# button.net
KiCad netlist of a schematic drawn in EAGLE
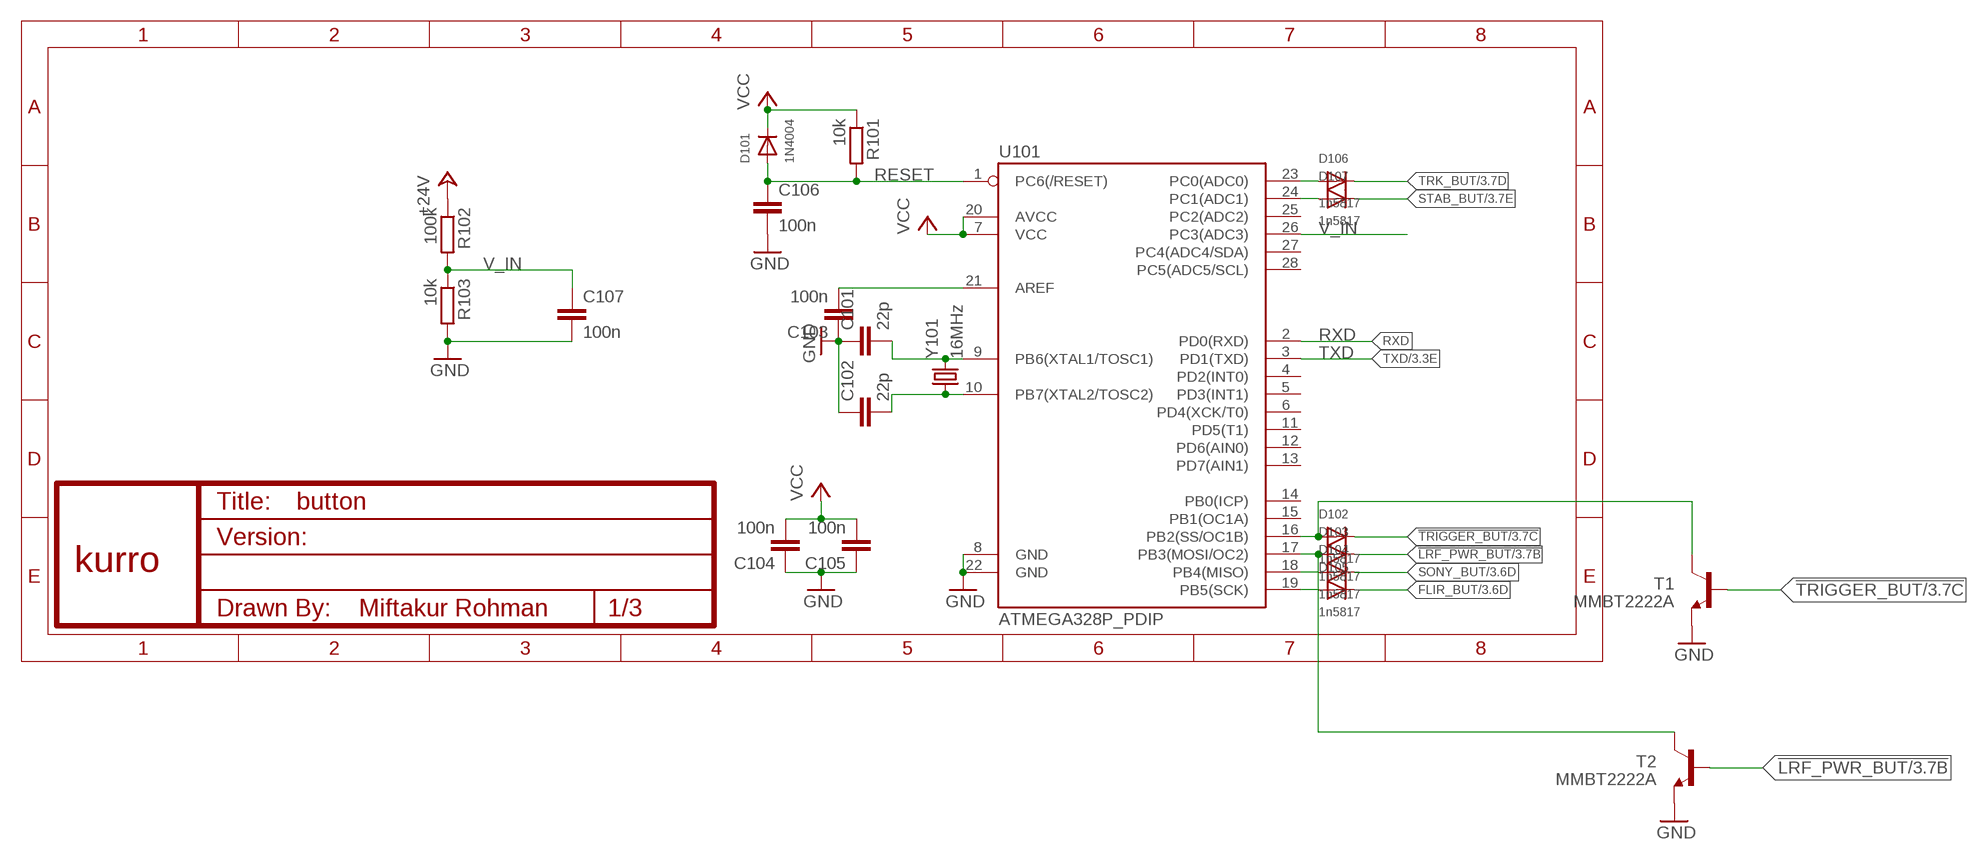
[diagram p0: schematic, sheet 1]
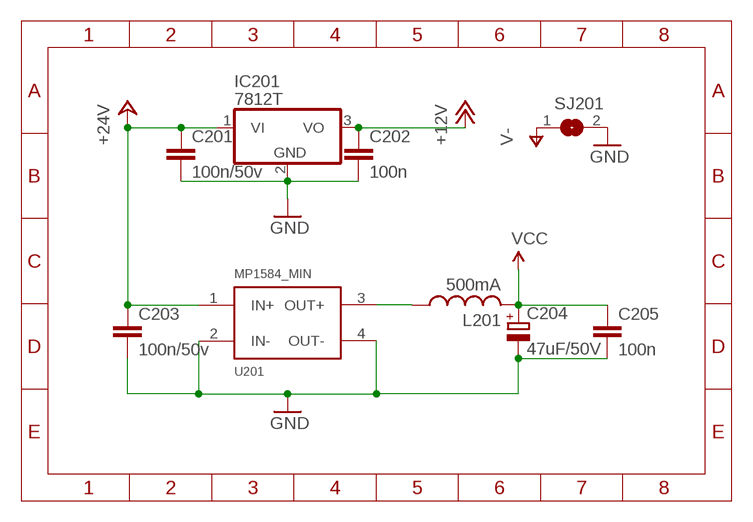
[diagram p1: schematic, sheet 2]
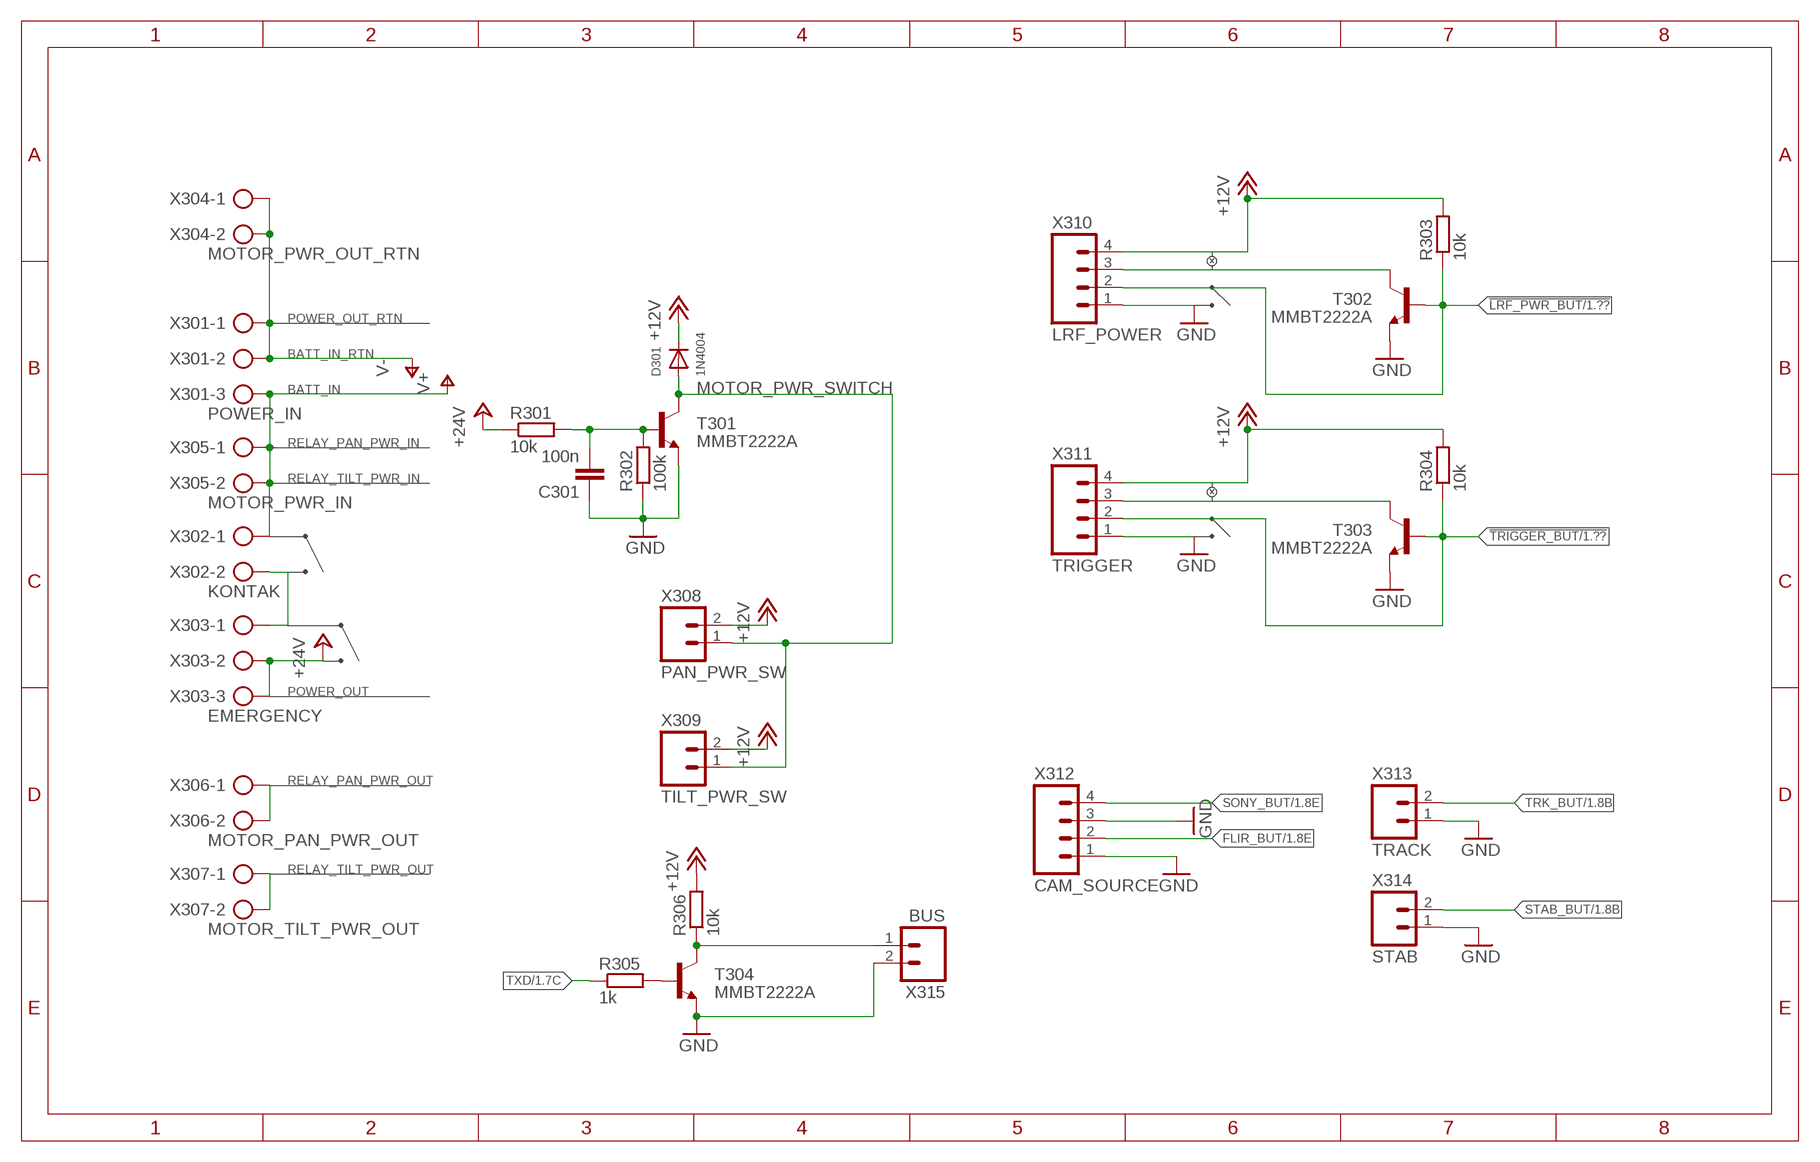
[diagram p2: schematic, sheet 3]

(export (version "E")
  (design (tool "Eeschema 10.0.6"))
  (components
    (comp (ref "C101")
      (value "22p")
      (footprint "eagle-import:C0603")
      (libsource (lib "eagle-import") (part "C-EUC0603"))
    )
    (comp (ref "C102")
      (value "22p")
      (footprint "eagle-import:C0603")
      (libsource (lib "eagle-import") (part "C-EUC0603"))
    )
    (comp (ref "C103")
      (value "100n")
      (footprint "eagle-import:C0603")
      (libsource (lib "eagle-import") (part "C-EUC0603"))
    )
    (comp (ref "C104")
      (value "100n")
      (footprint "eagle-import:C0603")
      (libsource (lib "eagle-import") (part "C-EUC0603"))
    )
    (comp (ref "C105")
      (value "100n")
      (footprint "eagle-import:C0603")
      (libsource (lib "eagle-import") (part "C-EUC0603"))
    )
    (comp (ref "C106")
      (value "100n")
      (footprint "eagle-import:C0603")
      (libsource (lib "eagle-import") (part "C-EUC0603"))
    )
    (comp (ref "C107")
      (value "100n")
      (footprint "eagle-import:C0603")
      (libsource (lib "eagle-import") (part "C-EUC0603"))
    )
    (comp (ref "D101")
      (value "1N4004")
      (footprint "eagle-import:SOD-323F")
      (libsource (lib "eagle-import") (part "DIODESOD-323F"))
    )
    (comp (ref "D102")
      (value "1n5817")
      (footprint "eagle-import:SOD-323F")
      (libsource (lib "eagle-import") (part "DIODESOD-323F"))
    )
    (comp (ref "D103")
      (value "1n5817")
      (footprint "eagle-import:SOD-323F")
      (libsource (lib "eagle-import") (part "DIODESOD-323F"))
    )
    (comp (ref "D104")
      (value "1n5817")
      (footprint "eagle-import:SOD-323F")
      (libsource (lib "eagle-import") (part "DIODESOD-323F"))
    )
    (comp (ref "D105")
      (value "1n5817")
      (footprint "eagle-import:SOD-323F")
      (libsource (lib "eagle-import") (part "DIODESOD-323F"))
    )
    (comp (ref "D106")
      (value "1n5817")
      (footprint "eagle-import:SOD-323F")
      (libsource (lib "eagle-import") (part "DIODESOD-323F"))
    )
    (comp (ref "D107")
      (value "1n5817")
      (footprint "eagle-import:SOD-323F")
      (libsource (lib "eagle-import") (part "DIODESOD-323F"))
    )
    (comp (ref "R101")
      (value "10k")
      (footprint "eagle-import:R0603")
      (libsource (lib "eagle-import") (part "R-EU_R0603"))
    )
    (comp (ref "R102")
      (value "100k")
      (footprint "eagle-import:R0603")
      (libsource (lib "eagle-import") (part "R-EU_R0603"))
    )
    (comp (ref "R103")
      (value "10k")
      (footprint "eagle-import:R0603")
      (libsource (lib "eagle-import") (part "R-EU_R0603"))
    )
    (comp (ref "T1")
      (value "MMBT2222A")
      (footprint "eagle-import:SOT23")
      (libsource (lib "eagle-import") (part "TRANSISTOR_NPNSOT23"))
    )
    (comp (ref "T2")
      (value "MMBT2222A")
      (footprint "eagle-import:SOT23")
      (libsource (lib "eagle-import") (part "TRANSISTOR_NPNSOT23"))
    )
    (comp (ref "U$1")
      (value "KURRO_FOOTPRINT")
      (footprint "eagle-import:KURRO-LOGO")
      (libsource (lib "eagle-import") (part "KURRO_FOOTPRINT"))
    )
    (comp (ref "U101")
      (value "ATMEGA328P_PDIP")
      (footprint "eagle-import:DIL28-3")
      (libsource (lib "eagle-import") (part "ATMEGA328P_PDIP"))
    )
    (comp (ref "Y101")
      (value "16MHz")
      (footprint "eagle-import:CRYSTAL-TXC-7A2")
      (libsource (lib "eagle-import") (part "CRYSTAL-TXC-7A2"))
    )
    (comp (ref "C301")
      (value "100n")
      (footprint "eagle-import:C0603")
      (libsource (lib "eagle-import") (part "C-EUC0603"))
    )
    (comp (ref "D301")
      (value "1N4004")
      (footprint "eagle-import:SOD-323F")
      (libsource (lib "eagle-import") (part "DIODESOD-323F"))
    )
    (comp (ref "R301")
      (value "10k")
      (footprint "eagle-import:R0603")
      (libsource (lib "eagle-import") (part "R-EU_R0603"))
    )
    (comp (ref "R302")
      (value "100k")
      (footprint "eagle-import:R0603")
      (libsource (lib "eagle-import") (part "R-EU_R0603"))
    )
    (comp (ref "R303")
      (value "10k")
      (footprint "eagle-import:R0603")
      (libsource (lib "eagle-import") (part "R-EU_R0603"))
    )
    (comp (ref "R304")
      (value "10k")
      (footprint "eagle-import:R0603")
      (libsource (lib "eagle-import") (part "R-EU_R0603"))
    )
    (comp (ref "R305")
      (value "1k")
      (footprint "eagle-import:R0603")
      (libsource (lib "eagle-import") (part "R-EU_R0603"))
    )
    (comp (ref "R306")
      (value "10k")
      (footprint "eagle-import:R0603")
      (libsource (lib "eagle-import") (part "R-EU_R0603"))
    )
    (comp (ref "T301")
      (value "MMBT2222A")
      (footprint "eagle-import:SOT23")
      (libsource (lib "eagle-import") (part "TRANSISTOR_NPNSOT23"))
    )
    (comp (ref "T302")
      (value "MMBT2222A")
      (footprint "eagle-import:SOT23")
      (libsource (lib "eagle-import") (part "TRANSISTOR_NPNSOT23"))
    )
    (comp (ref "T303")
      (value "MMBT2222A")
      (footprint "eagle-import:SOT23")
      (libsource (lib "eagle-import") (part "TRANSISTOR_NPNSOT23"))
    )
    (comp (ref "T304")
      (value "MMBT2222A")
      (footprint "eagle-import:SOT23")
      (libsource (lib "eagle-import") (part "TRANSISTOR_NPNSOT23"))
    )
    (comp (ref "X301")
      (value "POWER_IN")
      (footprint "eagle-import:AK300_3")
      (libsource (lib "eagle-import") (part "AK300/3"))
    )
    (comp (ref "X302")
      (value "KONTAK")
      (footprint "eagle-import:AK300_2")
      (libsource (lib "eagle-import") (part "AK300/2"))
    )
    (comp (ref "X303")
      (value "EMERGENCY")
      (footprint "eagle-import:AK300_3")
      (libsource (lib "eagle-import") (part "AK300/3"))
    )
    (comp (ref "X304")
      (value "MOTOR_PWR_OUT_RTN")
      (footprint "eagle-import:AK300_2")
      (libsource (lib "eagle-import") (part "AK300/2"))
    )
    (comp (ref "X305")
      (value "MOTOR_PWR_IN")
      (footprint "eagle-import:AK300_2")
      (libsource (lib "eagle-import") (part "AK300/2"))
    )
    (comp (ref "X306")
      (value "MOTOR_PAN_PWR_OUT")
      (footprint "eagle-import:AK300_2")
      (libsource (lib "eagle-import") (part "AK300/2"))
    )
    (comp (ref "X307")
      (value "MOTOR_TILT_PWR_OUT")
      (footprint "eagle-import:AK300_2")
      (libsource (lib "eagle-import") (part "AK300/2"))
    )
    (comp (ref "X308")
      (value "PAN_PWR_SW")
      (footprint "eagle-import:JST-2-PTH-VERT")
      (libsource (lib "eagle-import") (part "M02JST-PTH-VERT"))
    )
    (comp (ref "X309")
      (value "TILT_PWR_SW")
      (footprint "eagle-import:JST-2-PTH-VERT")
      (libsource (lib "eagle-import") (part "M02JST-PTH-VERT"))
    )
    (comp (ref "X310")
      (value "LRF_POWER")
      (footprint "eagle-import:JST-4-PTH-VERT")
      (libsource (lib "eagle-import") (part "M04JST-PTH-VERT"))
    )
    (comp (ref "X311")
      (value "TRIGGER")
      (footprint "eagle-import:JST-4-PTH-VERT")
      (libsource (lib "eagle-import") (part "M04JST-PTH-VERT"))
    )
    (comp (ref "X312")
      (value "CAM_SOURCE")
      (footprint "eagle-import:JST-4-PTH-VERT")
      (libsource (lib "eagle-import") (part "M04JST-PTH-VERT"))
    )
    (comp (ref "X313")
      (value "TRACK")
      (footprint "eagle-import:JST-2-PTH-VERT")
      (libsource (lib "eagle-import") (part "M02JST-PTH-VERT"))
    )
    (comp (ref "X314")
      (value "STAB")
      (footprint "eagle-import:JST-2-PTH-VERT")
      (libsource (lib "eagle-import") (part "M02JST-PTH-VERT"))
    )
    (comp (ref "X315")
      (value "BUS")
      (footprint "eagle-import:JST-2-PTH-VERT")
      (libsource (lib "eagle-import") (part "M02JST-PTH-VERT"))
    )
    (comp (ref "C201")
      (value "100n/50v")
      (footprint "eagle-import:C0603")
      (libsource (lib "eagle-import") (part "C-EUC0603"))
    )
    (comp (ref "C202")
      (value "100n")
      (footprint "eagle-import:C0603")
      (libsource (lib "eagle-import") (part "C-EUC0603"))
    )
    (comp (ref "C203")
      (value "100n/50v")
      (footprint "eagle-import:C0603")
      (libsource (lib "eagle-import") (part "C-EUC0603"))
    )
    (comp (ref "C204")
      (value "47uF/50V")
      (footprint "eagle-import:E2,5-7")
      (libsource (lib "eagle-import") (part "CPOL-EUE2.5-7"))
    )
    (comp (ref "C205")
      (value "100n")
      (footprint "eagle-import:C0603")
      (libsource (lib "eagle-import") (part "C-EUC0603"))
    )
    (comp (ref "IC201")
      (value "7812T")
      (footprint "eagle-import:TO220H")
      (libsource (lib "eagle-import") (part "78T12"))
    )
    (comp (ref "L201")
      (value "500mA")
      (footprint "eagle-import:L1812")
      (libsource (lib "eagle-import") (part "L-USL1812"))
    )
    (comp (ref "SJ201")
      (value "SJ")
      (footprint "eagle-import:SJ")
      (libsource (lib "eagle-import") (part "SJ"))
    )
    (comp (ref "U201")
      (value "MP1584_MIN")
      (footprint "eagle-import:MP1584_MIN")
      (libsource (lib "eagle-import") (part "MP1584_MIN"))
    )
  )
  (nets
    (net (code "1") (name "+12V") (class "Default")
      (node (ref "C202") (pin "1") (pinfunction "1_1") (pintype "passive"))
      (node (ref "D301") (pin "C") (pinfunction "C_C") (pintype "passive"))
      (node (ref "IC201") (pin "3") (pinfunction "VO_3") (pintype "passive"))
      (node (ref "R303") (pin "2") (pinfunction "2_2") (pintype "passive"))
      (node (ref "R304") (pin "2") (pinfunction "2_2") (pintype "passive"))
      (node (ref "R306") (pin "2") (pinfunction "2_2") (pintype "passive"))
      (node (ref "X308") (pin "2") (pinfunction "2_2") (pintype "passive"))
      (node (ref "X309") (pin "2") (pinfunction "2_2") (pintype "passive"))
      (node (ref "X310") (pin "4") (pinfunction "4_4") (pintype "passive"))
      (node (ref "X311") (pin "4") (pinfunction "4_4") (pintype "passive"))
    )
    (net (code "2") (name "+24V") (class "Default")
      (node (ref "C201") (pin "1") (pinfunction "1_1") (pintype "passive"))
      (node (ref "C203") (pin "1") (pinfunction "1_1") (pintype "passive"))
      (node (ref "IC201") (pin "1") (pinfunction "VI_1") (pintype "input"))
      (node (ref "R102") (pin "1") (pinfunction "1_1") (pintype "passive"))
      (node (ref "R301") (pin "1") (pinfunction "1_1") (pintype "passive"))
      (node (ref "U201") (pin "1") (pinfunction "IN+_1") (pintype "bidirectional"))
      (node (ref "X303") (pin "2") (pinfunction "KL_2") (pintype "passive"))
      (node (ref "X303") (pin "3") (pinfunction "KL_3") (pintype "passive"))
    )
    (net (code "3") (name "FLIR_BUT") (class "Default")
      (node (ref "D105") (pin "C") (pinfunction "C_C") (pintype "passive"))
      (node (ref "X312") (pin "2") (pinfunction "2_2") (pintype "passive"))
    )
    (net (code "4") (name "GND") (class "Default")
      (node (ref "C101") (pin "1") (pinfunction "1_1") (pintype "passive"))
      (node (ref "C102") (pin "1") (pinfunction "1_1") (pintype "passive"))
      (node (ref "C103") (pin "1") (pinfunction "1_1") (pintype "passive"))
      (node (ref "C104") (pin "1") (pinfunction "1_1") (pintype "passive"))
      (node (ref "C105") (pin "1") (pinfunction "1_1") (pintype "passive"))
      (node (ref "C106") (pin "2") (pinfunction "2_2") (pintype "passive"))
      (node (ref "C107") (pin "2") (pinfunction "2_2") (pintype "passive"))
      (node (ref "C201") (pin "2") (pinfunction "2_2") (pintype "passive"))
      (node (ref "C202") (pin "2") (pinfunction "2_2") (pintype "passive"))
      (node (ref "C203") (pin "2") (pinfunction "2_2") (pintype "passive"))
      (node (ref "C204") (pin "-") (pinfunction "-_-") (pintype "passive"))
      (node (ref "C205") (pin "2") (pinfunction "2_2") (pintype "passive"))
      (node (ref "C301") (pin "1") (pinfunction "1_1") (pintype "passive"))
      (node (ref "IC201") (pin "2") (pinfunction "GND_2") (pintype "passive"))
      (node (ref "R103") (pin "2") (pinfunction "2_2") (pintype "passive"))
      (node (ref "R302") (pin "1") (pinfunction "1_1") (pintype "passive"))
      (node (ref "SJ201") (pin "2") (pinfunction "2_2") (pintype "passive"))
      (node (ref "T1") (pin "2") (pinfunction "E_2") (pintype "passive"))
      (node (ref "T2") (pin "2") (pinfunction "E_2") (pintype "passive"))
      (node (ref "T301") (pin "2") (pinfunction "E_2") (pintype "passive"))
      (node (ref "T302") (pin "2") (pinfunction "E_2") (pintype "passive"))
      (node (ref "T303") (pin "2") (pinfunction "E_2") (pintype "passive"))
      (node (ref "T304") (pin "2") (pinfunction "E_2") (pintype "passive"))
      (node (ref "U101") (pin "22") (pinfunction "GND_22") (pintype "bidirectional"))
      (node (ref "U101") (pin "8") (pinfunction "GND_8") (pintype "bidirectional"))
      (node (ref "U201") (pin "2") (pinfunction "IN-_2") (pintype "bidirectional"))
      (node (ref "U201") (pin "4") (pinfunction "OUT-_4") (pintype "bidirectional"))
      (node (ref "X310") (pin "1") (pinfunction "1_1") (pintype "passive"))
      (node (ref "X311") (pin "1") (pinfunction "1_1") (pintype "passive"))
      (node (ref "X312") (pin "1") (pinfunction "1_1") (pintype "passive"))
      (node (ref "X312") (pin "3") (pinfunction "3_3") (pintype "passive"))
      (node (ref "X313") (pin "1") (pinfunction "1_1") (pintype "passive"))
      (node (ref "X314") (pin "1") (pinfunction "1_1") (pintype "passive"))
      (node (ref "X315") (pin "2") (pinfunction "2_2") (pintype "passive"))
    )
    (net (code "5") (name "MOTOR_PWR_SWITCH") (class "Default")
      (node (ref "D301") (pin "A") (pinfunction "A_A") (pintype "passive"))
      (node (ref "T301") (pin "3") (pinfunction "C_3") (pintype "passive"))
      (node (ref "X308") (pin "1") (pinfunction "1_1") (pintype "passive"))
      (node (ref "X309") (pin "1") (pinfunction "1_1") (pintype "passive"))
    )
    (net (code "6") (name "Net-(T1-C)") (class "Default")
      (node (ref "D102") (pin "A") (pinfunction "A_A") (pintype "passive"))
      (node (ref "T1") (pin "3") (pinfunction "C_3") (pintype "passive"))
      (node (ref "U101") (pin "16") (pinfunction "PB2(SS/OC1B)_16") (pintype "bidirectional"))
    )
    (net (code "7") (name "Net-(T2-C)") (class "Default")
      (node (ref "D103") (pin "A") (pinfunction "A_A") (pintype "passive"))
      (node (ref "T2") (pin "3") (pinfunction "C_3") (pintype "passive"))
      (node (ref "U101") (pin "17") (pinfunction "PB3(MOSI/OC2)_17") (pintype "bidirectional"))
    )
    (net (code "8") (name "Net-(T301-B)") (class "Default")
      (node (ref "C301") (pin "2") (pinfunction "2_2") (pintype "passive"))
      (node (ref "R301") (pin "2") (pinfunction "2_2") (pintype "passive"))
      (node (ref "R302") (pin "2") (pinfunction "2_2") (pintype "passive"))
      (node (ref "T301") (pin "1") (pinfunction "B_1") (pintype "passive"))
    )
    (net (code "9") (name "Net-(T302-C)") (class "Default")
      (node (ref "T302") (pin "3") (pinfunction "C_3") (pintype "passive"))
      (node (ref "X310") (pin "3") (pinfunction "3_3") (pintype "passive"))
    )
    (net (code "10") (name "Net-(T303-C)") (class "Default")
      (node (ref "T303") (pin "3") (pinfunction "C_3") (pintype "passive"))
      (node (ref "X311") (pin "3") (pinfunction "3_3") (pintype "passive"))
    )
    (net (code "11") (name "Net-(T304-B)") (class "Default")
      (node (ref "R305") (pin "2") (pinfunction "2_2") (pintype "passive"))
      (node (ref "T304") (pin "1") (pinfunction "B_1") (pintype "passive"))
    )
    (net (code "12") (name "Net-(T304-C)") (class "Default")
      (node (ref "R306") (pin "1") (pinfunction "1_1") (pintype "passive"))
      (node (ref "T304") (pin "3") (pinfunction "C_3") (pintype "passive"))
      (node (ref "X315") (pin "1") (pinfunction "1_1") (pintype "passive"))
    )
    (net (code "13") (name "Net-(U101-AREF)") (class "Default")
      (node (ref "C103") (pin "2") (pinfunction "2_2") (pintype "passive"))
      (node (ref "U101") (pin "21") (pinfunction "AREF_21") (pintype "bidirectional"))
    )
    (net (code "14") (name "Net-(U101-PB4(MISO))") (class "Default")
      (node (ref "D104") (pin "A") (pinfunction "A_A") (pintype "passive"))
      (node (ref "U101") (pin "18") (pinfunction "PB4(MISO)_18") (pintype "bidirectional"))
    )
    (net (code "15") (name "Net-(U101-PB5(SCK))") (class "Default")
      (node (ref "D105") (pin "A") (pinfunction "A_A") (pintype "passive"))
      (node (ref "U101") (pin "19") (pinfunction "PB5(SCK)_19") (pintype "bidirectional"))
    )
    (net (code "16") (name "Net-(U101-PB6(XTAL1{slash}TOSC1))") (class "Default")
      (node (ref "C101") (pin "2") (pinfunction "2_2") (pintype "passive"))
      (node (ref "U101") (pin "9") (pinfunction "PB6(XTAL1/TOSC1)_9") (pintype "bidirectional"))
      (node (ref "Y101") (pin "P$2") (pinfunction "2_P$2") (pintype "passive"))
    )
    (net (code "17") (name "Net-(U101-PB7(XTAL2{slash}TOSC2))") (class "Default")
      (node (ref "C102") (pin "2") (pinfunction "2_2") (pintype "passive"))
      (node (ref "U101") (pin "10") (pinfunction "PB7(XTAL2/TOSC2)_10") (pintype "bidirectional"))
      (node (ref "Y101") (pin "P$1") (pinfunction "1_P$1") (pintype "passive"))
    )
    (net (code "18") (name "Net-(U101-PC0(ADC0))") (class "Default")
      (node (ref "D106") (pin "A") (pinfunction "A_A") (pintype "passive"))
      (node (ref "U101") (pin "23") (pinfunction "PC0(ADC0)_23") (pintype "bidirectional"))
    )
    (net (code "19") (name "Net-(U101-PC1(ADC1))") (class "Default")
      (node (ref "D107") (pin "A") (pinfunction "A_A") (pintype "passive"))
      (node (ref "U101") (pin "24") (pinfunction "PC1(ADC1)_24") (pintype "bidirectional"))
    )
    (net (code "20") (name "Net-(U201-OUT+)") (class "Default")
      (node (ref "L201") (pin "1") (pinfunction "1_1") (pintype "passive"))
      (node (ref "U201") (pin "3") (pinfunction "OUT+_3") (pintype "bidirectional"))
    )
    (net (code "21") (name "Net-(X302B-KL)") (class "Default")
      (node (ref "X302") (pin "2") (pinfunction "KL_2") (pintype "passive"))
      (node (ref "X303") (pin "1") (pinfunction "KL_1") (pintype "passive"))
    )
    (net (code "22") (name "Net-(X306A-KL)") (class "Default")
      (node (ref "X306") (pin "1") (pinfunction "KL_1") (pintype "passive"))
      (node (ref "X306") (pin "2") (pinfunction "KL_2") (pintype "passive"))
    )
    (net (code "23") (name "Net-(X307A-KL)") (class "Default")
      (node (ref "X307") (pin "1") (pinfunction "KL_1") (pintype "passive"))
      (node (ref "X307") (pin "2") (pinfunction "KL_2") (pintype "passive"))
    )
    (net (code "24") (name "RESET") (class "Default")
      (node (ref "C106") (pin "1") (pinfunction "1_1") (pintype "passive"))
      (node (ref "D101") (pin "A") (pinfunction "A_A") (pintype "passive"))
      (node (ref "R101") (pin "2") (pinfunction "2_2") (pintype "passive"))
      (node (ref "U101") (pin "1") (pinfunction "PC6(/RESET)_1") (pintype "bidirectional"))
    )
    (net (code "25") (name "RXD") (class "Default")
      (node (ref "U101") (pin "2") (pinfunction "PD0(RXD)_2") (pintype "bidirectional"))
    )
    (net (code "26") (name "SONY_BUT") (class "Default")
      (node (ref "D104") (pin "C") (pinfunction "C_C") (pintype "passive"))
      (node (ref "X312") (pin "4") (pinfunction "4_4") (pintype "passive"))
    )
    (net (code "27") (name "STAB_BUT") (class "Default")
      (node (ref "D107") (pin "C") (pinfunction "C_C") (pintype "passive"))
      (node (ref "X314") (pin "2") (pinfunction "2_2") (pintype "passive"))
    )
    (net (code "28") (name "TRK_BUT") (class "Default")
      (node (ref "D106") (pin "C") (pinfunction "C_C") (pintype "passive"))
      (node (ref "X313") (pin "2") (pinfunction "2_2") (pintype "passive"))
    )
    (net (code "29") (name "TXD") (class "Default")
      (node (ref "R305") (pin "1") (pinfunction "1_1") (pintype "passive"))
      (node (ref "U101") (pin "3") (pinfunction "PD1(TXD)_3") (pintype "bidirectional"))
    )
    (net (code "30") (name "V+") (class "Default")
      (node (ref "X301") (pin "3") (pinfunction "KL_3") (pintype "passive"))
      (node (ref "X302") (pin "1") (pinfunction "KL_1") (pintype "passive"))
      (node (ref "X305") (pin "1") (pinfunction "KL_1") (pintype "passive"))
      (node (ref "X305") (pin "2") (pinfunction "KL_2") (pintype "passive"))
    )
    (net (code "31") (name "V-") (class "Default")
      (node (ref "SJ201") (pin "1") (pinfunction "1_1") (pintype "passive"))
      (node (ref "X301") (pin "1") (pinfunction "KL_1") (pintype "passive"))
      (node (ref "X301") (pin "2") (pinfunction "KL_2") (pintype "passive"))
      (node (ref "X304") (pin "1") (pinfunction "KL_1") (pintype "passive"))
      (node (ref "X304") (pin "2") (pinfunction "KL_2") (pintype "passive"))
    )
    (net (code "32") (name "VCC") (class "Default")
      (node (ref "C104") (pin "2") (pinfunction "2_2") (pintype "passive"))
      (node (ref "C105") (pin "2") (pinfunction "2_2") (pintype "passive"))
      (node (ref "C204") (pin "+") (pinfunction "+_+") (pintype "passive"))
      (node (ref "C205") (pin "1") (pinfunction "1_1") (pintype "passive"))
      (node (ref "D101") (pin "C") (pinfunction "C_C") (pintype "passive"))
      (node (ref "L201") (pin "2") (pinfunction "2_2") (pintype "passive"))
      (node (ref "R101") (pin "1") (pinfunction "1_1") (pintype "passive"))
      (node (ref "U101") (pin "20") (pinfunction "AVCC_20") (pintype "bidirectional"))
      (node (ref "U101") (pin "7") (pinfunction "VCC_7") (pintype "bidirectional"))
    )
    (net (code "33") (name "V_IN") (class "Default")
      (node (ref "C107") (pin "1") (pinfunction "1_1") (pintype "passive"))
      (node (ref "R102") (pin "2") (pinfunction "2_2") (pintype "passive"))
      (node (ref "R103") (pin "1") (pinfunction "1_1") (pintype "passive"))
      (node (ref "U101") (pin "26") (pinfunction "PC3(ADC3)_26") (pintype "bidirectional"))
    )
    (net (code "34") (name "unconnected-(U101-PB0(ICP)-Pad14)") (class "Default")
      (node (ref "U101") (pin "14") (pinfunction "PB0(ICP)_14") (pintype "bidirectional"))
    )
    (net (code "35") (name "unconnected-(U101-PB1(OC1A)-Pad15)") (class "Default")
      (node (ref "U101") (pin "15") (pinfunction "PB1(OC1A)_15") (pintype "bidirectional"))
    )
    (net (code "36") (name "unconnected-(U101-PC2(ADC2)-Pad25)") (class "Default")
      (node (ref "U101") (pin "25") (pinfunction "PC2(ADC2)_25") (pintype "bidirectional"))
    )
    (net (code "37") (name "unconnected-(U101-PC4(ADC4{slash}SDA)-Pad27)") (class "Default")
      (node (ref "U101") (pin "27") (pinfunction "PC4(ADC4/SDA)_27") (pintype "bidirectional"))
    )
    (net (code "38") (name "unconnected-(U101-PC5(ADC5{slash}SCL)-Pad28)") (class "Default")
      (node (ref "U101") (pin "28") (pinfunction "PC5(ADC5/SCL)_28") (pintype "bidirectional"))
    )
    (net (code "39") (name "unconnected-(U101-PD2(INT0)-Pad4)") (class "Default")
      (node (ref "U101") (pin "4") (pinfunction "PD2(INT0)_4") (pintype "bidirectional"))
    )
    (net (code "40") (name "unconnected-(U101-PD3(INT1)-Pad5)") (class "Default")
      (node (ref "U101") (pin "5") (pinfunction "PD3(INT1)_5") (pintype "bidirectional"))
    )
    (net (code "41") (name "unconnected-(U101-PD4(XCK{slash}T0)-Pad6)") (class "Default")
      (node (ref "U101") (pin "6") (pinfunction "PD4(XCK/T0)_6") (pintype "bidirectional"))
    )
    (net (code "42") (name "unconnected-(U101-PD5(T1)-Pad11)") (class "Default")
      (node (ref "U101") (pin "11") (pinfunction "PD5(T1)_11") (pintype "bidirectional"))
    )
    (net (code "43") (name "unconnected-(U101-PD6(AIN0)-Pad12)") (class "Default")
      (node (ref "U101") (pin "12") (pinfunction "PD6(AIN0)_12") (pintype "bidirectional"))
    )
    (net (code "44") (name "unconnected-(U101-PD7(AIN1)-Pad13)") (class "Default")
      (node (ref "U101") (pin "13") (pinfunction "PD7(AIN1)_13") (pintype "bidirectional"))
    )
    (net (code "45") (name "~{LRF_PWR_BUT}") (class "Default")
      (node (ref "D103") (pin "C") (pinfunction "C_C") (pintype "passive"))
      (node (ref "R303") (pin "1") (pinfunction "1_1") (pintype "passive"))
      (node (ref "T2") (pin "1") (pinfunction "B_1") (pintype "passive"))
      (node (ref "T302") (pin "1") (pinfunction "B_1") (pintype "passive"))
      (node (ref "X310") (pin "2") (pinfunction "2_2") (pintype "passive"))
    )
    (net (code "46") (name "~{TRIGGER_BUT}") (class "Default")
      (node (ref "D102") (pin "C") (pinfunction "C_C") (pintype "passive"))
      (node (ref "R304") (pin "1") (pinfunction "1_1") (pintype "passive"))
      (node (ref "T1") (pin "1") (pinfunction "B_1") (pintype "passive"))
      (node (ref "T303") (pin "1") (pinfunction "B_1") (pintype "passive"))
      (node (ref "X311") (pin "2") (pinfunction "2_2") (pintype "passive"))
    )
  )
)
